# brain.net
KiCad netlist of a schematic drawn in EAGLE
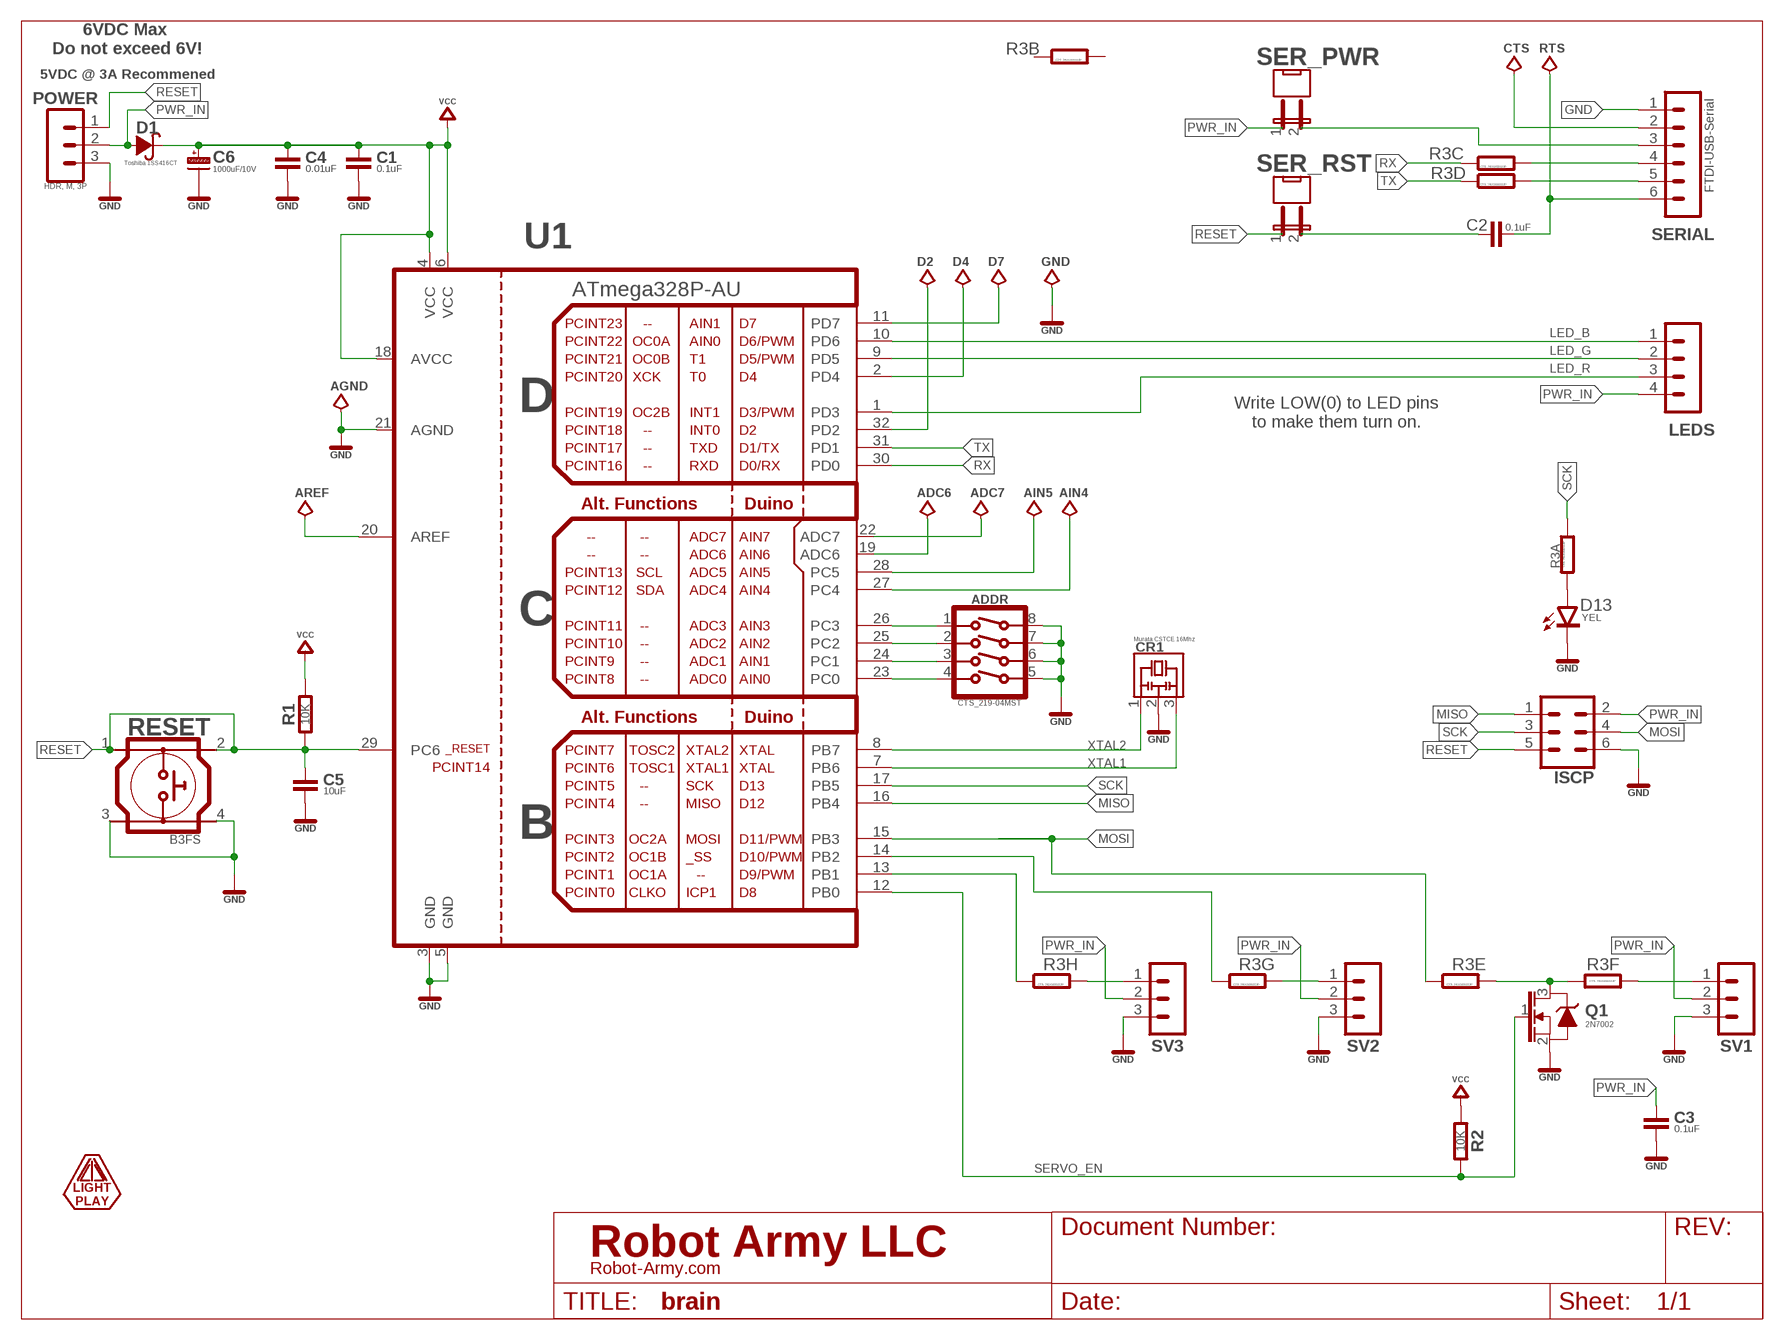
[diagram p0: schematic, sheet 1]

(export (version "E")
  (design (tool "Eeschema 10.0.6"))
  (components
    (comp (ref "ADC6")
      (value "TEST_POINT_SM_2X2")
      (footprint "eagle-import:TP-SMT-020X020")
      (libsource (lib "eagle-import") (part "TEST_POINT_SM_2X2"))
    )
    (comp (ref "ADC7")
      (value "TEST_POINT_SM_2X2")
      (footprint "eagle-import:TP-SMT-020X020")
      (libsource (lib "eagle-import") (part "TEST_POINT_SM_2X2"))
    )
    (comp (ref "ADDR")
      (value "CTS_219-04MST")
      (footprint "eagle-import:CTS_4P_GULLWING")
      (libsource (lib "eagle-import") (part "DIP-4PCTS-219-SMD"))
    )
    (comp (ref "AGND")
      (value "TEST_POINT_SM_2X2")
      (footprint "eagle-import:TP-SMT-020X020")
      (libsource (lib "eagle-import") (part "TEST_POINT_SM_2X2"))
    )
    (comp (ref "AIN4")
      (value "TEST_POINT_SM_2X2")
      (footprint "eagle-import:TP-SMT-020X020")
      (libsource (lib "eagle-import") (part "TEST_POINT_SM_2X2"))
    )
    (comp (ref "AIN5")
      (value "TEST_POINT_SM_2X2")
      (footprint "eagle-import:TP-SMT-020X020")
      (libsource (lib "eagle-import") (part "TEST_POINT_SM_2X2"))
    )
    (comp (ref "AREF")
      (value "TEST_POINT_SM_2X2")
      (footprint "eagle-import:TP-SMT-020X020")
      (libsource (lib "eagle-import") (part "TEST_POINT_SM_2X2"))
    )
    (comp (ref "C1")
      (value "0.1uF")
      (footprint "eagle-import:0603")
      (libsource (lib "eagle-import") (part "CAPACITOR0603"))
    )
    (comp (ref "C2")
      (value "0.1uF")
      (footprint "eagle-import:0603")
      (libsource (lib "eagle-import") (part "CAPACITOR0603"))
    )
    (comp (ref "C3")
      (value "0.1uF")
      (footprint "eagle-import:0603")
      (libsource (lib "eagle-import") (part "CAPACITOR0603"))
    )
    (comp (ref "C4")
      (value "0.01uF")
      (footprint "eagle-import:0603")
      (libsource (lib "eagle-import") (part "CAPACITOR0603"))
    )
    (comp (ref "C5")
      (value "10uF")
      (footprint "eagle-import:0805")
      (libsource (lib "eagle-import") (part "CAPACITOR0805"))
    )
    (comp (ref "C6")
      (value "1000uF/10V")
      (footprint "eagle-import:CAP_ALUM_THD_8")
      (libsource (lib "eagle-import") (part "CAPACITOR_POLCAP_ALUM_THD_8"))
    )
    (comp (ref "CR1")
      (value "Murata CSTCE 16Mhz")
      (footprint "eagle-import:MURATA_CSTCE")
      (libsource (lib "eagle-import") (part "RESONATORMURATA-CSTCE"))
    )
    (comp (ref "CTS")
      (value "TEST_POINT_SM_2X2")
      (footprint "eagle-import:TP-SMT-020X020")
      (libsource (lib "eagle-import") (part "TEST_POINT_SM_2X2"))
    )
    (comp (ref "D1")
      (value "Toshiba 1SS416CT")
      (footprint "eagle-import:CST2")
      (libsource (lib "eagle-import") (part "SCHOTTKYTOSHIBA_CST2"))
    )
    (comp (ref "D2")
      (value "TEST_POINT_SM_2X2")
      (footprint "eagle-import:TP-SMT-020X020")
      (libsource (lib "eagle-import") (part "TEST_POINT_SM_2X2"))
    )
    (comp (ref "D4")
      (value "TEST_POINT_SM_2X2")
      (footprint "eagle-import:TP-SMT-020X020")
      (libsource (lib "eagle-import") (part "TEST_POINT_SM_2X2"))
    )
    (comp (ref "D7")
      (value "TEST_POINT_SM_2X2")
      (footprint "eagle-import:TP-SMT-020X020")
      (libsource (lib "eagle-import") (part "TEST_POINT_SM_2X2"))
    )
    (comp (ref "D13")
      (value "YEL")
      (footprint "eagle-import:SMD_0603")
      (libsource (lib "eagle-import") (part "SMT0603"))
    )
    (comp (ref "GND")
      (value "TEST_POINT_SM_2X2")
      (footprint "eagle-import:TP-SMT-020X020")
      (libsource (lib "eagle-import") (part "TEST_POINT_SM_2X2"))
    )
    (comp (ref "ISCP")
      (value "MA03-2")
      (footprint "eagle-import:MA03-2")
      (libsource (lib "eagle-import") (part "MA03-2"))
    )
    (comp (ref "LEDS")
      (value "MA04-1")
      (footprint "eagle-import:MA04-1")
      (libsource (lib "eagle-import") (part "MA04-1"))
    )
    (comp (ref "LOGO2")
      (value "LIGHT_PLAY_20MM")
      (footprint "eagle-import:LIGHTPLAY_20MM")
      (libsource (lib "eagle-import") (part "LIGHT_PLAY_20MM"))
    )
    (comp (ref "POWER")
      (value "HDR, M, 3P")
      (footprint "eagle-import:MA03-1")
      (libsource (lib "eagle-import") (part "MA03-1"))
    )
    (comp (ref "Q1")
      (value "2N7002")
      (footprint "eagle-import:SOT-23")
      (libsource (lib "eagle-import") (part "SOT23_2N7002"))
    )
    (comp (ref "R1")
      (value "10K")
      (footprint "eagle-import:0603")
      (libsource (lib "eagle-import") (part "RESISTOR0603"))
    )
    (comp (ref "R2")
      (value "10K")
      (footprint "eagle-import:0603")
      (libsource (lib "eagle-import") (part "RESISTOR0603"))
    )
    (comp (ref "R3")
      (value "CTS 741X163102JP")
      (footprint "eagle-import:RESNET_0402_X8")
      (libsource (lib "eagle-import") (part "RESNET_0402_INDIV_X8"))
    )
    (comp (ref "RESET")
      (value "B3FS")
      (footprint "eagle-import:B3FS")
      (libsource (lib "eagle-import") (part "PUSHBTN-SP-MOM-4PINB3FS"))
    )
    (comp (ref "RTS")
      (value "TEST_POINT_SM_2X2")
      (footprint "eagle-import:TP-SMT-020X020")
      (libsource (lib "eagle-import") (part "TEST_POINT_SM_2X2"))
    )
    (comp (ref "SERIAL")
      (value "MA06-1")
      (footprint "eagle-import:MA06-1")
      (libsource (lib "eagle-import") (part "MA06-1"))
    )
    (comp (ref "SER_PWR")
      (value "JMP01VT")
      (footprint "eagle-import:MA02-1-FAT")
      (libsource (lib "eagle-import") (part "JMP01VT"))
    )
    (comp (ref "SER_RST")
      (value "JMP01VT")
      (footprint "eagle-import:MA02-1-FAT")
      (libsource (lib "eagle-import") (part "JMP01VT"))
    )
    (comp (ref "SV1")
      (value "MA03-1")
      (footprint "eagle-import:MA03-1")
      (libsource (lib "eagle-import") (part "MA03-1"))
    )
    (comp (ref "SV2")
      (value "MA03-1")
      (footprint "eagle-import:MA03-1")
      (libsource (lib "eagle-import") (part "MA03-1"))
    )
    (comp (ref "SV3")
      (value "MA03-1")
      (footprint "eagle-import:MA03-1")
      (libsource (lib "eagle-import") (part "MA03-1"))
    )
    (comp (ref "U1")
      (value "ATmega328P-AU")
      (footprint "eagle-import:TQFP-32-08")
      (libsource (lib "eagle-import") (part "ATMEGA328"))
    )
  )
  (nets
    (net (code "1") (name "/LED_B") (class "Default")
      (node (ref "LEDS") (pin "1") (pinfunction "1_1") (pintype "passive"))
      (node (ref "U1") (pin "10") (pinfunction "PD6_10") (pintype "bidirectional"))
    )
    (net (code "2") (name "/LED_G") (class "Default")
      (node (ref "LEDS") (pin "2") (pinfunction "2_2") (pintype "passive"))
      (node (ref "U1") (pin "9") (pinfunction "PD5_9") (pintype "bidirectional"))
    )
    (net (code "3") (name "/LED_R") (class "Default")
      (node (ref "LEDS") (pin "3") (pinfunction "3_3") (pintype "passive"))
      (node (ref "U1") (pin "1") (pinfunction "PD3_1") (pintype "bidirectional"))
    )
    (net (code "4") (name "/SERVO_EN") (class "Default")
      (node (ref "Q1") (pin "1") (pinfunction "G_1") (pintype "bidirectional"))
      (node (ref "R2") (pin "2") (pinfunction "2_2") (pintype "passive"))
      (node (ref "U1") (pin "12") (pinfunction "PB0_12") (pintype "bidirectional"))
    )
    (net (code "5") (name "/XTAL1") (class "Default")
      (node (ref "CR1") (pin "3") (pinfunction "3_3") (pintype "bidirectional"))
      (node (ref "U1") (pin "7") (pinfunction "PB6_7") (pintype "bidirectional"))
    )
    (net (code "6") (name "/XTAL2") (class "Default")
      (node (ref "CR1") (pin "1") (pinfunction "1_1") (pintype "bidirectional"))
      (node (ref "U1") (pin "8") (pinfunction "PB7_8") (pintype "bidirectional"))
    )
    (net (code "7") (name "GND") (class "Default")
      (node (ref "ADDR") (pin "5") (pinfunction "5_5") (pintype "bidirectional"))
      (node (ref "ADDR") (pin "6") (pinfunction "6_6") (pintype "bidirectional"))
      (node (ref "ADDR") (pin "7") (pinfunction "7_7") (pintype "bidirectional"))
      (node (ref "ADDR") (pin "8") (pinfunction "8_8") (pintype "bidirectional"))
      (node (ref "AGND") (pin "1") (pinfunction "P$1_1") (pintype "bidirectional"))
      (node (ref "C1") (pin "2") (pinfunction "2_2") (pintype "passive"))
      (node (ref "C3") (pin "2") (pinfunction "2_2") (pintype "passive"))
      (node (ref "C4") (pin "2") (pinfunction "2_2") (pintype "passive"))
      (node (ref "C5") (pin "2") (pinfunction "2_2") (pintype "passive"))
      (node (ref "C6") (pin "N") (pinfunction "N_N") (pintype "bidirectional"))
      (node (ref "CR1") (pin "2") (pinfunction "2_2") (pintype "bidirectional"))
      (node (ref "D13") (pin "K") (pinfunction "C_K") (pintype "passive"))
      (node (ref "GND") (pin "1") (pinfunction "P$1_1") (pintype "bidirectional"))
      (node (ref "ISCP") (pin "6") (pinfunction "6_6") (pintype "passive"))
      (node (ref "POWER") (pin "3") (pinfunction "3_3") (pintype "passive"))
      (node (ref "Q1") (pin "2") (pinfunction "S_2") (pintype "bidirectional"))
      (node (ref "RESET") (pin "3") (pinfunction "3_3") (pintype "bidirectional"))
      (node (ref "RESET") (pin "4") (pinfunction "4_4") (pintype "bidirectional"))
      (node (ref "SERIAL") (pin "1") (pinfunction "1_1") (pintype "passive"))
      (node (ref "SV1") (pin "3") (pinfunction "3_3") (pintype "passive"))
      (node (ref "SV2") (pin "3") (pinfunction "3_3") (pintype "passive"))
      (node (ref "SV3") (pin "3") (pinfunction "3_3") (pintype "passive"))
      (node (ref "U1") (pin "21") (pinfunction "AGND_21") (pintype "power_in"))
      (node (ref "U1") (pin "3") (pinfunction "GND_3") (pintype "power_in"))
      (node (ref "U1") (pin "5") (pinfunction "GND_5") (pintype "power_in"))
    )
    (net (code "8") (name "MISO") (class "Default")
      (node (ref "ISCP") (pin "1") (pinfunction "1_1") (pintype "passive"))
      (node (ref "U1") (pin "16") (pinfunction "PB4_16") (pintype "bidirectional"))
    )
    (net (code "9") (name "MOSI") (class "Default")
      (node (ref "ISCP") (pin "4") (pinfunction "4_4") (pintype "passive"))
      (node (ref "R3") (pin "5") (pinfunction "1_5") (pintype "passive"))
      (node (ref "U1") (pin "15") (pinfunction "PB3_15") (pintype "bidirectional"))
    )
    (net (code "10") (name "Net-(ADC6-P$1)") (class "Default")
      (node (ref "ADC6") (pin "1") (pinfunction "P$1_1") (pintype "bidirectional"))
      (node (ref "U1") (pin "19") (pinfunction "ADC6_19") (pintype "bidirectional"))
    )
    (net (code "11") (name "Net-(ADC7-P$1)") (class "Default")
      (node (ref "ADC7") (pin "1") (pinfunction "P$1_1") (pintype "bidirectional"))
      (node (ref "U1") (pin "22") (pinfunction "ADC7_22") (pintype "bidirectional"))
    )
    (net (code "12") (name "Net-(AIN4-P$1)") (class "Default")
      (node (ref "AIN4") (pin "1") (pinfunction "P$1_1") (pintype "bidirectional"))
      (node (ref "U1") (pin "27") (pinfunction "PC4_27") (pintype "bidirectional"))
    )
    (net (code "13") (name "Net-(AIN5-P$1)") (class "Default")
      (node (ref "AIN5") (pin "1") (pinfunction "P$1_1") (pintype "bidirectional"))
      (node (ref "U1") (pin "28") (pinfunction "PC5_28") (pintype "bidirectional"))
    )
    (net (code "14") (name "Net-(AREF-P$1)") (class "Default")
      (node (ref "AREF") (pin "1") (pinfunction "P$1_1") (pintype "bidirectional"))
      (node (ref "U1") (pin "20") (pinfunction "AREF_20") (pintype "input"))
    )
    (net (code "15") (name "Net-(CTS-P$1)") (class "Default")
      (node (ref "CTS") (pin "1") (pinfunction "P$1_1") (pintype "bidirectional"))
      (node (ref "SERIAL") (pin "2") (pinfunction "2_2") (pintype "passive"))
    )
    (net (code "16") (name "Net-(D2-P$1)") (class "Default")
      (node (ref "D2") (pin "1") (pinfunction "P$1_1") (pintype "bidirectional"))
      (node (ref "U1") (pin "32") (pinfunction "PD2_32") (pintype "bidirectional"))
    )
    (net (code "17") (name "Net-(D4-P$1)") (class "Default")
      (node (ref "D4") (pin "1") (pinfunction "P$1_1") (pintype "bidirectional"))
      (node (ref "U1") (pin "2") (pinfunction "PD4_2") (pintype "bidirectional"))
    )
    (net (code "18") (name "Net-(D7-P$1)") (class "Default")
      (node (ref "D7") (pin "1") (pinfunction "P$1_1") (pintype "bidirectional"))
      (node (ref "U1") (pin "11") (pinfunction "PD7_11") (pintype "bidirectional"))
    )
    (net (code "19") (name "Net-(Q1-D)") (class "Default")
      (node (ref "Q1") (pin "3") (pinfunction "D_3") (pintype "bidirectional"))
      (node (ref "R3") (pin "11") (pinfunction "2_11") (pintype "passive"))
      (node (ref "R3") (pin "12") (pinfunction "2_12") (pintype "passive"))
    )
    (net (code "20") (name "Net-(R3A-2)") (class "Default")
      (node (ref "D13") (pin "A") (pinfunction "A_A") (pintype "passive"))
      (node (ref "R3") (pin "16") (pinfunction "2_16") (pintype "passive"))
    )
    (net (code "21") (name "Net-(R3C-2)") (class "Default")
      (node (ref "R3") (pin "14") (pinfunction "2_14") (pintype "passive"))
      (node (ref "SERIAL") (pin "4") (pinfunction "4_4") (pintype "passive"))
    )
    (net (code "22") (name "Net-(R3D-2)") (class "Default")
      (node (ref "R3") (pin "13") (pinfunction "2_13") (pintype "passive"))
      (node (ref "SERIAL") (pin "5") (pinfunction "5_5") (pintype "passive"))
    )
    (net (code "23") (name "Net-(R3F-1)") (class "Default")
      (node (ref "R3") (pin "6") (pinfunction "1_6") (pintype "passive"))
      (node (ref "SV1") (pin "1") (pinfunction "1_1") (pintype "passive"))
    )
    (net (code "24") (name "Net-(R3G-1)") (class "Default")
      (node (ref "R3") (pin "7") (pinfunction "1_7") (pintype "passive"))
      (node (ref "U1") (pin "14") (pinfunction "PB2_14") (pintype "bidirectional"))
    )
    (net (code "25") (name "Net-(R3G-2)") (class "Default")
      (node (ref "R3") (pin "10") (pinfunction "2_10") (pintype "passive"))
      (node (ref "SV2") (pin "1") (pinfunction "1_1") (pintype "passive"))
    )
    (net (code "26") (name "Net-(R3H-1)") (class "Default")
      (node (ref "R3") (pin "8") (pinfunction "1_8") (pintype "passive"))
      (node (ref "U1") (pin "13") (pinfunction "PB1_13") (pintype "bidirectional"))
    )
    (net (code "27") (name "Net-(R3H-2)") (class "Default")
      (node (ref "R3") (pin "9") (pinfunction "2_9") (pintype "passive"))
      (node (ref "SV3") (pin "1") (pinfunction "1_1") (pintype "passive"))
    )
    (net (code "28") (name "Net-(RTS-P$1)") (class "Default")
      (node (ref "C2") (pin "2") (pinfunction "2_2") (pintype "passive"))
      (node (ref "RTS") (pin "1") (pinfunction "P$1_1") (pintype "bidirectional"))
      (node (ref "SERIAL") (pin "6") (pinfunction "6_6") (pintype "passive"))
    )
    (net (code "29") (name "Net-(SER_PWR-P$2)") (class "Default")
      (node (ref "SERIAL") (pin "3") (pinfunction "3_3") (pintype "passive"))
      (node (ref "SER_PWR") (pin "2") (pinfunction "P$2_2") (pintype "bidirectional"))
    )
    (net (code "30") (name "Net-(SER_RST-P$2)") (class "Default")
      (node (ref "C2") (pin "1") (pinfunction "1_1") (pintype "passive"))
      (node (ref "SER_RST") (pin "2") (pinfunction "P$2_2") (pintype "bidirectional"))
    )
    (net (code "31") (name "Net-(U1-PC0)") (class "Default")
      (node (ref "ADDR") (pin "4") (pinfunction "4_4") (pintype "bidirectional"))
      (node (ref "U1") (pin "23") (pinfunction "PC0_23") (pintype "bidirectional"))
    )
    (net (code "32") (name "Net-(U1-PC1)") (class "Default")
      (node (ref "ADDR") (pin "3") (pinfunction "3_3") (pintype "bidirectional"))
      (node (ref "U1") (pin "24") (pinfunction "PC1_24") (pintype "bidirectional"))
    )
    (net (code "33") (name "Net-(U1-PC2)") (class "Default")
      (node (ref "ADDR") (pin "2") (pinfunction "2_2") (pintype "bidirectional"))
      (node (ref "U1") (pin "25") (pinfunction "PC2_25") (pintype "bidirectional"))
    )
    (net (code "34") (name "Net-(U1-PC3)") (class "Default")
      (node (ref "ADDR") (pin "1") (pinfunction "1_1") (pintype "bidirectional"))
      (node (ref "U1") (pin "26") (pinfunction "PC3_26") (pintype "bidirectional"))
    )
    (net (code "35") (name "PWR_IN") (class "Default")
      (node (ref "C3") (pin "1") (pinfunction "1_1") (pintype "passive"))
      (node (ref "D1") (pin "A") (pinfunction "A_A") (pintype "passive"))
      (node (ref "ISCP") (pin "2") (pinfunction "2_2") (pintype "passive"))
      (node (ref "LEDS") (pin "4") (pinfunction "4_4") (pintype "passive"))
      (node (ref "POWER") (pin "2") (pinfunction "2_2") (pintype "passive"))
      (node (ref "SER_PWR") (pin "1") (pinfunction "P$1_1") (pintype "bidirectional"))
      (node (ref "SV1") (pin "2") (pinfunction "2_2") (pintype "passive"))
      (node (ref "SV2") (pin "2") (pinfunction "2_2") (pintype "passive"))
      (node (ref "SV3") (pin "2") (pinfunction "2_2") (pintype "passive"))
    )
    (net (code "36") (name "RESET") (class "Default")
      (node (ref "C5") (pin "1") (pinfunction "1_1") (pintype "passive"))
      (node (ref "ISCP") (pin "5") (pinfunction "5_5") (pintype "passive"))
      (node (ref "POWER") (pin "1") (pinfunction "1_1") (pintype "passive"))
      (node (ref "R1") (pin "1") (pinfunction "1_1") (pintype "passive"))
      (node (ref "RESET") (pin "1") (pinfunction "1_1") (pintype "bidirectional"))
      (node (ref "RESET") (pin "2") (pinfunction "2_2") (pintype "bidirectional"))
      (node (ref "SER_RST") (pin "1") (pinfunction "P$1_1") (pintype "bidirectional"))
      (node (ref "U1") (pin "29") (pinfunction "PC6_29") (pintype "bidirectional"))
    )
    (net (code "37") (name "RX") (class "Default")
      (node (ref "R3") (pin "3") (pinfunction "1_3") (pintype "passive"))
      (node (ref "U1") (pin "30") (pinfunction "PD0_30") (pintype "bidirectional"))
    )
    (net (code "38") (name "SCK") (class "Default")
      (node (ref "ISCP") (pin "3") (pinfunction "3_3") (pintype "passive"))
      (node (ref "R3") (pin "1") (pinfunction "1_1") (pintype "passive"))
      (node (ref "U1") (pin "17") (pinfunction "PB5_17") (pintype "bidirectional"))
    )
    (net (code "39") (name "TX") (class "Default")
      (node (ref "R3") (pin "4") (pinfunction "1_4") (pintype "passive"))
      (node (ref "U1") (pin "31") (pinfunction "PD1_31") (pintype "bidirectional"))
    )
    (net (code "40") (name "VCC") (class "Default")
      (node (ref "C1") (pin "1") (pinfunction "1_1") (pintype "passive"))
      (node (ref "C4") (pin "1") (pinfunction "1_1") (pintype "passive"))
      (node (ref "C6") (pin "P") (pinfunction "P_P") (pintype "bidirectional"))
      (node (ref "D1") (pin "K") (pinfunction "K_K") (pintype "passive"))
      (node (ref "R1") (pin "2") (pinfunction "2_2") (pintype "passive"))
      (node (ref "R2") (pin "1") (pinfunction "1_1") (pintype "passive"))
      (node (ref "U1") (pin "18") (pinfunction "AVCC_18") (pintype "power_in"))
      (node (ref "U1") (pin "4") (pinfunction "VCC_4") (pintype "power_in"))
      (node (ref "U1") (pin "6") (pinfunction "VCC_6") (pintype "power_in"))
    )
    (net (code "41") (name "unconnected-(R3B-1-Pad2)") (class "Default")
      (node (ref "R3") (pin "2") (pinfunction "1_2") (pintype "passive"))
    )
    (net (code "42") (name "unconnected-(R3B-2-Pad15)") (class "Default")
      (node (ref "R3") (pin "15") (pinfunction "2_15") (pintype "passive"))
    )
  )
)
